# communication_module_20190819_to_aj-doy.net
KiCad netlist of a schematic drawn in EAGLE
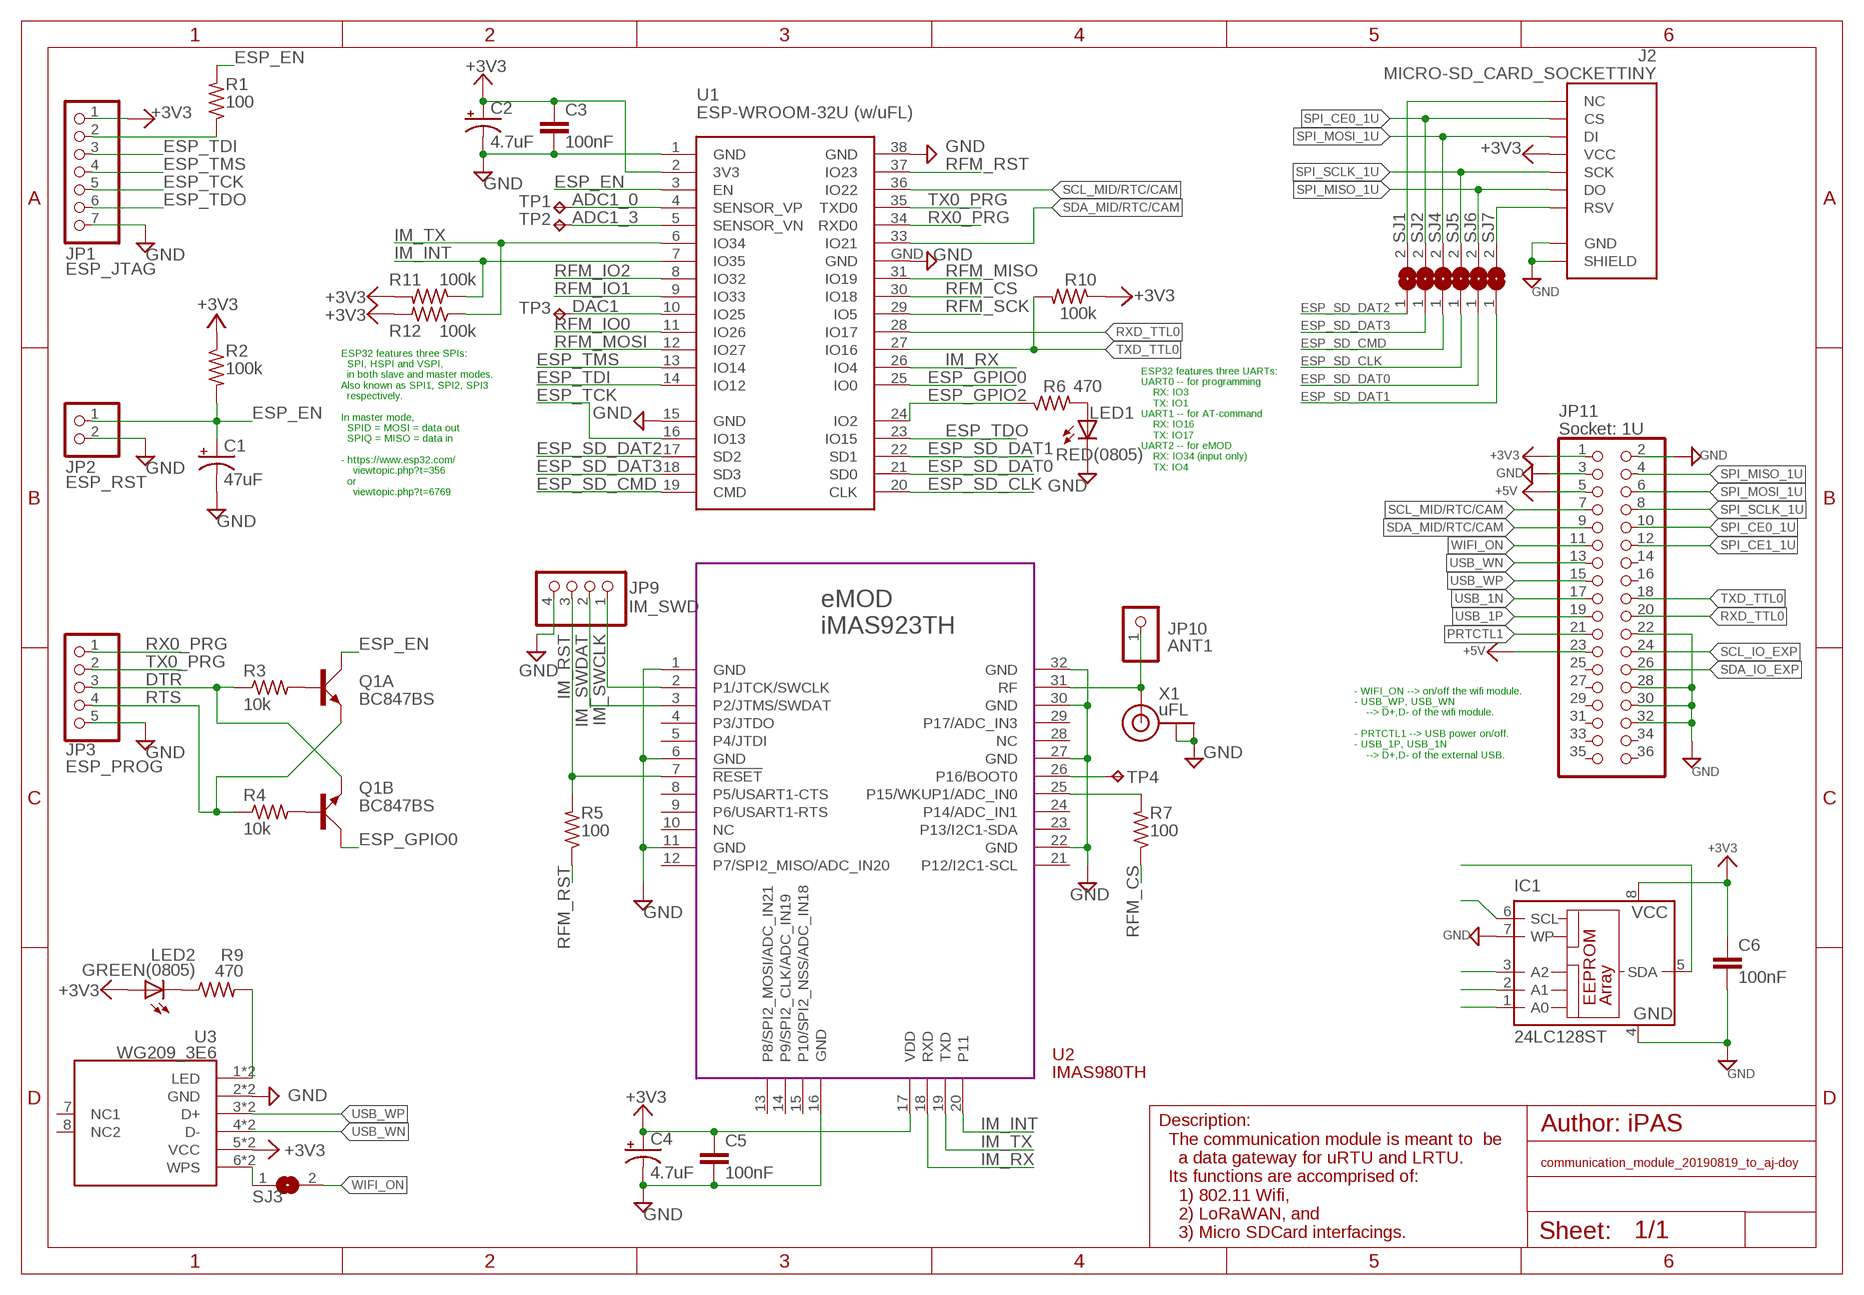
[diagram p0: schematic, sheet 1]

(export (version "E")
  (design (tool "Eeschema 10.0.6"))
  (components
    (comp (ref "C1")
      (value "47uF")
      (footprint "eagle-import:RCL_150CLZ-1014")
      (libsource (lib "eagle-import") (part "RCL_CPOL-US150CLZ-1014"))
    )
    (comp (ref "C2")
      (value "4.7uF")
      (footprint "eagle-import:RCL_150CLZ-1014")
      (libsource (lib "eagle-import") (part "RCL_CPOL-US150CLZ-1014"))
    )
    (comp (ref "C3")
      (value "100nF")
      (footprint "eagle-import:RCL_C1206")
      (libsource (lib "eagle-import") (part "RCL_C-EUC1206"))
    )
    (comp (ref "C4")
      (value "4.7uF")
      (footprint "eagle-import:RCL_150CLZ-1014")
      (libsource (lib "eagle-import") (part "RCL_CPOL-US150CLZ-1014"))
    )
    (comp (ref "C5")
      (value "100nF")
      (footprint "eagle-import:RCL_C1206")
      (libsource (lib "eagle-import") (part "RCL_C-EUC1206"))
    )
    (comp (ref "C6")
      (value "100nF")
      (footprint "eagle-import:RCL_C1206")
      (libsource (lib "eagle-import") (part "RCL_C-EUC1206"))
    )
    (comp (ref "IC1")
      (value "24LC128ST")
      (footprint "eagle-import:TSSOP8")
      (fields (field (name "MF") "MICROCHIP") (field (name "MPN") "24LC128-I/ST"))
      (libsource (lib "eagle-import") (part "24STLC128"))
    )
    (comp (ref "J2")
      (value "MICRO-SD_CARD_SOCKETTINY")
      (footprint "eagle-import:MICROSD_TINY")
      (libsource (lib "eagle-import") (part "MICRO-SD_CARD_SOCKETTINY"))
    )
    (comp (ref "JP1")
      (value "ESP_JTAG")
      (footprint "eagle-import:1X07")
      (libsource (lib "eagle-import") (part "PINHD-1X7"))
    )
    (comp (ref "JP2")
      (value "ESP_RST")
      (footprint "eagle-import:1X02")
      (libsource (lib "eagle-import") (part "PINHD-1X2"))
    )
    (comp (ref "JP3")
      (value "ESP_PROG")
      (footprint "eagle-import:1X05")
      (libsource (lib "eagle-import") (part "PINHD-1X5"))
    )
    (comp (ref "JP9")
      (value "IM_SWD")
      (footprint "eagle-import:1X04")
      (libsource (lib "eagle-import") (part "PINHD-1X4"))
    )
    (comp (ref "JP10")
      (value "ANT1")
      (footprint "eagle-import:1X01_ROUND")
      (libsource (lib "eagle-import") (part "HEADER-1X1ROUND"))
    )
    (comp (ref "JP11")
      (value "Socket: 1U")
      (footprint "eagle-import:2X18")
      (libsource (lib "eagle-import") (part "PINHD-2X18"))
    )
    (comp (ref "LED1")
      (value "RED(0805)")
      (footprint "eagle-import:CHIP-LED0805")
      (libsource (lib "eagle-import") (part "LEDCHIP-LED0805"))
    )
    (comp (ref "LED2")
      (value "GREEN(0805)")
      (footprint "eagle-import:CHIP-LED0805")
      (libsource (lib "eagle-import") (part "LEDCHIP-LED0805"))
    )
    (comp (ref "Q1")
      (value "BC847BS")
      (footprint "eagle-import:SOT363_PHILIPS")
      (libsource (lib "eagle-import") (part "BC847BS"))
    )
    (comp (ref "R1")
      (value "100")
      (footprint "eagle-import:RCL_M0805")
      (libsource (lib "eagle-import") (part "RCL_R-USM0805"))
    )
    (comp (ref "R2")
      (value "100k")
      (footprint "eagle-import:RCL_M0805")
      (libsource (lib "eagle-import") (part "RCL_R-USM0805"))
    )
    (comp (ref "R3")
      (value "10k")
      (footprint "eagle-import:RCL_M0805")
      (libsource (lib "eagle-import") (part "RCL_R-USM0805"))
    )
    (comp (ref "R4")
      (value "10k")
      (footprint "eagle-import:RCL_M0805")
      (libsource (lib "eagle-import") (part "RCL_R-USM0805"))
    )
    (comp (ref "R5")
      (value "100")
      (footprint "eagle-import:RCL_M0805")
      (libsource (lib "eagle-import") (part "RCL_R-USM0805"))
    )
    (comp (ref "R6")
      (value "470")
      (footprint "eagle-import:RCL_M0805")
      (libsource (lib "eagle-import") (part "RCL_R-USM0805"))
    )
    (comp (ref "R7")
      (value "100")
      (footprint "eagle-import:RCL_M0805")
      (libsource (lib "eagle-import") (part "RCL_R-USM0805"))
    )
    (comp (ref "R9")
      (value "470")
      (footprint "eagle-import:RCL_M0805")
      (libsource (lib "eagle-import") (part "RCL_R-USM0805"))
    )
    (comp (ref "R10")
      (value "100k")
      (footprint "eagle-import:RCL_M0805")
      (libsource (lib "eagle-import") (part "RCL_R-USM0805"))
    )
    (comp (ref "R11")
      (value "100k")
      (footprint "eagle-import:RCL_M0805")
      (libsource (lib "eagle-import") (part "RCL_R-USM0805"))
    )
    (comp (ref "R12")
      (value "100k")
      (footprint "eagle-import:RCL_M0805")
      (libsource (lib "eagle-import") (part "RCL_R-USM0805"))
    )
    (comp (ref "SJ1")
      (value "SOLDERJUMPERREFLOW")
      (footprint "eagle-import:SOLDERJUMPER_REFLOW")
      (libsource (lib "eagle-import") (part "SOLDERJUMPERREFLOW"))
    )
    (comp (ref "SJ2")
      (value "SOLDERJUMPERREFLOW")
      (footprint "eagle-import:SOLDERJUMPER_REFLOW")
      (libsource (lib "eagle-import") (part "SOLDERJUMPERREFLOW"))
    )
    (comp (ref "SJ3")
      (value "SOLDERJUMPERREFLOW")
      (footprint "eagle-import:SOLDERJUMPER_REFLOW")
      (libsource (lib "eagle-import") (part "SOLDERJUMPERREFLOW"))
    )
    (comp (ref "SJ4")
      (value "SOLDERJUMPERREFLOW")
      (footprint "eagle-import:SOLDERJUMPER_REFLOW")
      (libsource (lib "eagle-import") (part "SOLDERJUMPERREFLOW"))
    )
    (comp (ref "SJ5")
      (value "SOLDERJUMPERREFLOW")
      (footprint "eagle-import:SOLDERJUMPER_REFLOW")
      (libsource (lib "eagle-import") (part "SOLDERJUMPERREFLOW"))
    )
    (comp (ref "SJ6")
      (value "SOLDERJUMPERREFLOW")
      (footprint "eagle-import:SOLDERJUMPER_REFLOW")
      (libsource (lib "eagle-import") (part "SOLDERJUMPERREFLOW"))
    )
    (comp (ref "SJ7")
      (value "SOLDERJUMPERREFLOW")
      (footprint "eagle-import:SOLDERJUMPER_REFLOW")
      (libsource (lib "eagle-import") (part "SOLDERJUMPERREFLOW"))
    )
    (comp (ref "TP1")
      (value "TPB1,27")
      (footprint "eagle-import:B1,27")
      (libsource (lib "eagle-import") (part "TPB1,27"))
    )
    (comp (ref "TP2")
      (value "TPB1,27")
      (footprint "eagle-import:B1,27")
      (libsource (lib "eagle-import") (part "TPB1,27"))
    )
    (comp (ref "TP3")
      (value "TPB1,27")
      (footprint "eagle-import:B1,27")
      (libsource (lib "eagle-import") (part "TPB1,27"))
    )
    (comp (ref "TP4")
      (value "TPB1,27")
      (footprint "eagle-import:B1,27")
      (libsource (lib "eagle-import") (part "TPB1,27"))
    )
    (comp (ref "U1")
      (value "ESP-WROOM-32U (w/uFL)")
      (footprint "eagle-import:ESP-WROOM-32")
      (libsource (lib "eagle-import") (part "ESP-WROOM-32"))
    )
    (comp (ref "U2")
      (value "IMAS980TH")
      (footprint "eagle-import:IMAS923TH")
      (libsource (lib "eagle-import") (part "IMAS980TH"))
    )
    (comp (ref "U3")
      (value "WG209_3E6")
      (footprint "eagle-import:WG209")
      (libsource (lib "eagle-import") (part "WG209"))
    )
    (comp (ref "X1")
      (value "uFL")
      (footprint "eagle-import:U.FL")
      (libsource (lib "eagle-import") (part "ANTENNA_U.FL"))
    )
  )
  (nets
    (net (code "1") (name "+3V3") (class "Default")
      (node (ref "C2") (pin "+") (pinfunction "+_+") (pintype "passive"))
      (node (ref "C3") (pin "1") (pinfunction "1_1") (pintype "passive"))
      (node (ref "C4") (pin "+") (pinfunction "+_+") (pintype "passive"))
      (node (ref "C5") (pin "1") (pinfunction "1_1") (pintype "passive"))
      (node (ref "C6") (pin "1") (pinfunction "1_1") (pintype "passive"))
      (node (ref "IC1") (pin "8") (pinfunction "VCC_8") (pintype "power_in"))
      (node (ref "J2") (pin "4") (pinfunction "VCC_4") (pintype "bidirectional"))
      (node (ref "JP1") (pin "1") (pinfunction "1_1") (pintype "passive"))
      (node (ref "JP11") (pin "1") (pinfunction "1_1") (pintype "passive"))
      (node (ref "LED2") (pin "A") (pinfunction "A_A") (pintype "passive"))
      (node (ref "R10") (pin "1") (pinfunction "1_1") (pintype "passive"))
      (node (ref "R11") (pin "2") (pinfunction "2_2") (pintype "passive"))
      (node (ref "R12") (pin "2") (pinfunction "2_2") (pintype "passive"))
      (node (ref "R2") (pin "1") (pinfunction "1_1") (pintype "passive"))
      (node (ref "U1") (pin "2") (pinfunction "3V3_2") (pintype "power_in"))
      (node (ref "U2") (pin "17") (pinfunction "VDD_17") (pintype "power_in"))
      (node (ref "U3") (pin "5") (pinfunction "VCC_5") (pintype "power_in"))
      (node (ref "U3") (pin "5P") (pinfunction "VCC_5P") (pintype "power_in"))
    )
    (net (code "2") (name "+5V") (class "Default")
      (node (ref "JP11") (pin "23") (pinfunction "23_23") (pintype "passive"))
      (node (ref "JP11") (pin "5") (pinfunction "5_5") (pintype "passive"))
    )
    (net (code "3") (name "/ADC1_0") (class "Default")
      (node (ref "TP1") (pin "TP") (pinfunction "TP_TP") (pintype "input"))
      (node (ref "U1") (pin "4") (pinfunction "SENSOR_VP_4") (pintype "bidirectional"))
    )
    (net (code "4") (name "/ADC1_3") (class "Default")
      (node (ref "TP2") (pin "TP") (pinfunction "TP_TP") (pintype "input"))
      (node (ref "U1") (pin "5") (pinfunction "SENSOR_VN_5") (pintype "bidirectional"))
    )
    (net (code "5") (name "/DAC1") (class "Default")
      (node (ref "TP3") (pin "TP") (pinfunction "TP_TP") (pintype "input"))
      (node (ref "U1") (pin "10") (pinfunction "IO25_10") (pintype "bidirectional"))
    )
    (net (code "6") (name "/DTR") (class "Default")
      (node (ref "JP3") (pin "3") (pinfunction "3_3") (pintype "passive"))
      (node (ref "Q1") (pin "4") (pinfunction "E_4") (pintype "passive"))
      (node (ref "R3") (pin "1") (pinfunction "1_1") (pintype "passive"))
    )
    (net (code "7") (name "/ESP_EN") (class "Default")
      (node (ref "C1") (pin "+") (pinfunction "+_+") (pintype "passive"))
      (node (ref "JP2") (pin "1") (pinfunction "1_1") (pintype "passive"))
      (node (ref "Q1") (pin "6") (pinfunction "C_6") (pintype "passive"))
      (node (ref "R1") (pin "2") (pinfunction "2_2") (pintype "passive"))
      (node (ref "R2") (pin "2") (pinfunction "2_2") (pintype "passive"))
      (node (ref "U1") (pin "3") (pinfunction "EN_3") (pintype "input"))
    )
    (net (code "8") (name "/ESP_GPIO0") (class "Default")
      (node (ref "Q1") (pin "3") (pinfunction "C_3") (pintype "passive"))
      (node (ref "U1") (pin "25") (pinfunction "IO0_25") (pintype "bidirectional"))
    )
    (net (code "9") (name "/ESP_GPIO2") (class "Default")
      (node (ref "R6") (pin "1") (pinfunction "1_1") (pintype "passive"))
      (node (ref "U1") (pin "24") (pinfunction "IO2_24") (pintype "bidirectional"))
    )
    (net (code "10") (name "/ESP_SD_CLK") (class "Default")
      (node (ref "SJ5") (pin "1") (pinfunction "1_1") (pintype "passive"))
      (node (ref "U1") (pin "20") (pinfunction "CLK_20") (pintype "bidirectional"))
    )
    (net (code "11") (name "/ESP_SD_CMD") (class "Default")
      (node (ref "SJ4") (pin "1") (pinfunction "1_1") (pintype "passive"))
      (node (ref "U1") (pin "19") (pinfunction "CMD_19") (pintype "bidirectional"))
    )
    (net (code "12") (name "/ESP_SD_DAT0") (class "Default")
      (node (ref "SJ6") (pin "1") (pinfunction "1_1") (pintype "passive"))
      (node (ref "U1") (pin "21") (pinfunction "SD0_21") (pintype "bidirectional"))
    )
    (net (code "13") (name "/ESP_SD_DAT1") (class "Default")
      (node (ref "SJ7") (pin "1") (pinfunction "1_1") (pintype "passive"))
      (node (ref "U1") (pin "22") (pinfunction "SD1_22") (pintype "bidirectional"))
    )
    (net (code "14") (name "/ESP_SD_DAT2") (class "Default")
      (node (ref "SJ1") (pin "1") (pinfunction "1_1") (pintype "passive"))
      (node (ref "U1") (pin "17") (pinfunction "SD2_17") (pintype "bidirectional"))
    )
    (net (code "15") (name "/ESP_SD_DAT3") (class "Default")
      (node (ref "SJ2") (pin "1") (pinfunction "1_1") (pintype "passive"))
      (node (ref "U1") (pin "18") (pinfunction "SD3_18") (pintype "bidirectional"))
    )
    (net (code "16") (name "/ESP_TCK") (class "Default")
      (node (ref "JP1") (pin "5") (pinfunction "5_5") (pintype "passive"))
      (node (ref "U1") (pin "16") (pinfunction "IO13_16") (pintype "bidirectional"))
    )
    (net (code "17") (name "/ESP_TDI") (class "Default")
      (node (ref "JP1") (pin "3") (pinfunction "3_3") (pintype "passive"))
      (node (ref "U1") (pin "14") (pinfunction "IO12_14") (pintype "bidirectional"))
    )
    (net (code "18") (name "/ESP_TDO") (class "Default")
      (node (ref "JP1") (pin "6") (pinfunction "6_6") (pintype "passive"))
      (node (ref "U1") (pin "23") (pinfunction "IO15_23") (pintype "bidirectional"))
    )
    (net (code "19") (name "/ESP_TMS") (class "Default")
      (node (ref "JP1") (pin "4") (pinfunction "4_4") (pintype "passive"))
      (node (ref "U1") (pin "13") (pinfunction "IO14_13") (pintype "bidirectional"))
    )
    (net (code "20") (name "/IM_INT") (class "Default")
      (node (ref "R11") (pin "1") (pinfunction "1_1") (pintype "passive"))
      (node (ref "U1") (pin "7") (pinfunction "IO35_7") (pintype "bidirectional"))
      (node (ref "U2") (pin "20") (pinfunction "P11_20") (pintype "bidirectional"))
    )
    (net (code "21") (name "/IM_RST") (class "Default")
      (node (ref "JP9") (pin "3") (pinfunction "3_3") (pintype "passive"))
      (node (ref "R5") (pin "2") (pinfunction "2_2") (pintype "passive"))
      (node (ref "U2") (pin "7") (pinfunction "~{RESET}_7") (pintype "passive"))
    )
    (net (code "22") (name "/IM_RX") (class "Default")
      (node (ref "U1") (pin "26") (pinfunction "IO4_26") (pintype "bidirectional"))
      (node (ref "U2") (pin "18") (pinfunction "RXD_18") (pintype "bidirectional"))
    )
    (net (code "23") (name "/IM_SWCLK") (class "Default")
      (node (ref "JP9") (pin "1") (pinfunction "1_1") (pintype "passive"))
      (node (ref "U2") (pin "2") (pinfunction "P1/JTCK/SWCLK_2") (pintype "bidirectional"))
    )
    (net (code "24") (name "/IM_SWDAT") (class "Default")
      (node (ref "JP9") (pin "2") (pinfunction "2_2") (pintype "passive"))
      (node (ref "U2") (pin "3") (pinfunction "P2/JTMS/SWDAT_3") (pintype "bidirectional"))
    )
    (net (code "25") (name "/IM_TX") (class "Default")
      (node (ref "R12") (pin "1") (pinfunction "1_1") (pintype "passive"))
      (node (ref "U1") (pin "6") (pinfunction "IO34_6") (pintype "bidirectional"))
      (node (ref "U2") (pin "19") (pinfunction "TXD_19") (pintype "bidirectional"))
    )
    (net (code "26") (name "/RFM_CS") (class "Default")
      (node (ref "R7") (pin "1") (pinfunction "1_1") (pintype "passive"))
      (node (ref "U1") (pin "30") (pinfunction "IO18_30") (pintype "bidirectional"))
    )
    (net (code "27") (name "/RFM_IO0") (class "Default")
      (node (ref "U1") (pin "11") (pinfunction "IO26_11") (pintype "bidirectional"))
    )
    (net (code "28") (name "/RFM_IO1") (class "Default")
      (node (ref "U1") (pin "9") (pinfunction "IO33_9") (pintype "bidirectional"))
    )
    (net (code "29") (name "/RFM_IO2") (class "Default")
      (node (ref "U1") (pin "8") (pinfunction "IO32_8") (pintype "bidirectional"))
    )
    (net (code "30") (name "/RFM_MISO") (class "Default")
      (node (ref "U1") (pin "31") (pinfunction "IO19_31") (pintype "bidirectional"))
    )
    (net (code "31") (name "/RFM_MOSI") (class "Default")
      (node (ref "U1") (pin "12") (pinfunction "IO27_12") (pintype "bidirectional"))
    )
    (net (code "32") (name "/RFM_RST") (class "Default")
      (node (ref "R5") (pin "1") (pinfunction "1_1") (pintype "passive"))
      (node (ref "U1") (pin "37") (pinfunction "IO23_37") (pintype "bidirectional"))
    )
    (net (code "33") (name "/RFM_SCK") (class "Default")
      (node (ref "U1") (pin "29") (pinfunction "IO5_29") (pintype "bidirectional"))
    )
    (net (code "34") (name "/RTS") (class "Default")
      (node (ref "JP3") (pin "4") (pinfunction "4_4") (pintype "passive"))
      (node (ref "Q1") (pin "1") (pinfunction "E_1") (pintype "passive"))
      (node (ref "R4") (pin "1") (pinfunction "1_1") (pintype "passive"))
    )
    (net (code "35") (name "/RX0_PRG") (class "Default")
      (node (ref "JP3") (pin "1") (pinfunction "1_1") (pintype "passive"))
      (node (ref "U1") (pin "34") (pinfunction "RXD0_34") (pintype "bidirectional"))
    )
    (net (code "36") (name "/TX0_PRG") (class "Default")
      (node (ref "JP3") (pin "2") (pinfunction "2_2") (pintype "passive"))
      (node (ref "U1") (pin "35") (pinfunction "TXD0_35") (pintype "bidirectional"))
    )
    (net (code "37") (name "GND") (class "Default")
      (node (ref "C1") (pin "-") (pinfunction "-_-") (pintype "passive"))
      (node (ref "C2") (pin "-") (pinfunction "-_-") (pintype "passive"))
      (node (ref "C3") (pin "2") (pinfunction "2_2") (pintype "passive"))
      (node (ref "C4") (pin "-") (pinfunction "-_-") (pintype "passive"))
      (node (ref "C5") (pin "2") (pinfunction "2_2") (pintype "passive"))
      (node (ref "C6") (pin "2") (pinfunction "2_2") (pintype "passive"))
      (node (ref "IC1") (pin "4") (pinfunction "GND_4") (pintype "power_in"))
      (node (ref "IC1") (pin "7") (pinfunction "WP_7") (pintype "input"))
      (node (ref "J2") (pin "6") (pinfunction "GND_6") (pintype "bidirectional"))
      (node (ref "J2") (pin "GND1") (pinfunction "SHIELD_GND1") (pintype "bidirectional"))
      (node (ref "J2") (pin "GND2") (pinfunction "SHIELD_GND2") (pintype "bidirectional"))
      (node (ref "J2") (pin "GND3") (pinfunction "SHIELD_GND3") (pintype "bidirectional"))
      (node (ref "J2") (pin "GND4") (pinfunction "SHIELD_GND4") (pintype "bidirectional"))
      (node (ref "J2") (pin "GND5") (pinfunction "SHIELD_GND5") (pintype "bidirectional"))
      (node (ref "J2") (pin "GND6") (pinfunction "SHIELD_GND6") (pintype "bidirectional"))
      (node (ref "JP1") (pin "7") (pinfunction "7_7") (pintype "passive"))
      (node (ref "JP11") (pin "2") (pinfunction "2_2") (pintype "passive"))
      (node (ref "JP11") (pin "22") (pinfunction "22_22") (pintype "passive"))
      (node (ref "JP11") (pin "28") (pinfunction "28_28") (pintype "passive"))
      (node (ref "JP11") (pin "3") (pinfunction "3_3") (pintype "passive"))
      (node (ref "JP11") (pin "30") (pinfunction "30_30") (pintype "passive"))
      (node (ref "JP11") (pin "32") (pinfunction "32_32") (pintype "passive"))
      (node (ref "JP2") (pin "2") (pinfunction "2_2") (pintype "passive"))
      (node (ref "JP3") (pin "5") (pinfunction "5_5") (pintype "passive"))
      (node (ref "JP9") (pin "4") (pinfunction "4_4") (pintype "passive"))
      (node (ref "LED1") (pin "C") (pinfunction "C_C") (pintype "passive"))
      (node (ref "U1") (pin "1") (pinfunction "GND_1") (pintype "power_in"))
      (node (ref "U1") (pin "15") (pinfunction "GND_15") (pintype "power_in"))
      (node (ref "U1") (pin "38") (pinfunction "GND_38") (pintype "power_in"))
      (node (ref "U1") (pin "GND") (pinfunction "GND_GND") (pintype "power_in"))
      (node (ref "U2") (pin "1") (pinfunction "GND_1") (pintype "power_in"))
      (node (ref "U2") (pin "11") (pinfunction "GND_11") (pintype "power_in"))
      (node (ref "U2") (pin "16") (pinfunction "GND_16") (pintype "power_in"))
      (node (ref "U2") (pin "22") (pinfunction "GND_22") (pintype "power_in"))
      (node (ref "U2") (pin "27") (pinfunction "GND_27") (pintype "power_in"))
      (node (ref "U2") (pin "30") (pinfunction "GND_30") (pintype "power_in"))
      (node (ref "U2") (pin "32") (pinfunction "GND_32") (pintype "power_in"))
      (node (ref "U2") (pin "6") (pinfunction "GND_6") (pintype "power_in"))
      (node (ref "U3") (pin "2") (pinfunction "GND_2") (pintype "power_in"))
      (node (ref "U3") (pin "2P") (pinfunction "GND_2P") (pintype "power_in"))
      (node (ref "X1") (pin "1") (pinfunction "GND_1") (pintype "passive"))
      (node (ref "X1") (pin "2") (pinfunction "GND_2") (pintype "passive"))
    )
    (net (code "38") (name "Net-(J2-NC)") (class "Default")
      (node (ref "J2") (pin "9") (pinfunction "NC_9") (pintype "bidirectional"))
      (node (ref "SJ1") (pin "2") (pinfunction "2_2") (pintype "passive"))
    )
    (net (code "39") (name "Net-(J2-RSV-Pad1)") (class "Default")
      (node (ref "J2") (pin "1") (pinfunction "RSV_1") (pintype "bidirectional"))
      (node (ref "J2") (pin "8") (pinfunction "RSV_8") (pintype "bidirectional"))
      (node (ref "SJ7") (pin "2") (pinfunction "2_2") (pintype "passive"))
    )
    (net (code "40") (name "Net-(JP1-Pad2)") (class "Default")
      (node (ref "JP1") (pin "2") (pinfunction "2_2") (pintype "passive"))
      (node (ref "R1") (pin "1") (pinfunction "1_1") (pintype "passive"))
    )
    (net (code "41") (name "Net-(LED1-PadA)") (class "Default")
      (node (ref "LED1") (pin "A") (pinfunction "A_A") (pintype "passive"))
      (node (ref "R6") (pin "2") (pinfunction "2_2") (pintype "passive"))
    )
    (net (code "42") (name "Net-(LED2-PadC)") (class "Default")
      (node (ref "LED2") (pin "C") (pinfunction "C_C") (pintype "passive"))
      (node (ref "R9") (pin "1") (pinfunction "1_1") (pintype "passive"))
    )
    (net (code "43") (name "Net-(Q1A-B)") (class "Default")
      (node (ref "Q1") (pin "2") (pinfunction "B_2") (pintype "passive"))
      (node (ref "R3") (pin "2") (pinfunction "2_2") (pintype "passive"))
    )
    (net (code "44") (name "Net-(Q1B-B)") (class "Default")
      (node (ref "Q1") (pin "5") (pinfunction "B_5") (pintype "passive"))
      (node (ref "R4") (pin "2") (pinfunction "2_2") (pintype "passive"))
    )
    (net (code "45") (name "Net-(R9-Pad2)") (class "Default")
      (node (ref "R9") (pin "2") (pinfunction "2_2") (pintype "passive"))
      (node (ref "U3") (pin "1") (pinfunction "LED_1") (pintype "bidirectional"))
      (node (ref "U3") (pin "1P") (pinfunction "LED_1P") (pintype "bidirectional"))
    )
    (net (code "46") (name "Net-(SJ3-Pad1)") (class "Default")
      (node (ref "SJ3") (pin "1") (pinfunction "1_1") (pintype "passive"))
      (node (ref "U3") (pin "6") (pinfunction "WPS_6") (pintype "bidirectional"))
      (node (ref "U3") (pin "6P") (pinfunction "WPS_6P") (pintype "bidirectional"))
    )
    (net (code "47") (name "Net-(U2-P15{slash}WKUP1{slash}ADC_IN0)") (class "Default")
      (node (ref "R7") (pin "2") (pinfunction "2_2") (pintype "passive"))
      (node (ref "U2") (pin "25") (pinfunction "P15/WKUP1/ADC_IN0_25") (pintype "bidirectional"))
    )
    (net (code "48") (name "Net-(U2-P16{slash}BOOT0)") (class "Default")
      (node (ref "TP4") (pin "TP") (pinfunction "TP_TP") (pintype "input"))
      (node (ref "U2") (pin "26") (pinfunction "P16/BOOT0_26") (pintype "passive"))
    )
    (net (code "49") (name "Net-(U2-RF)") (class "Default")
      (node (ref "JP10") (pin "1") (pinfunction "1_1") (pintype "passive"))
      (node (ref "U2") (pin "31") (pinfunction "RF_31") (pintype "bidirectional"))
      (node (ref "X1") (pin "3") (pinfunction "SIGNAL_3") (pintype "passive"))
    )
    (net (code "50") (name "PRTCTL1") (class "Default")
      (node (ref "JP11") (pin "21") (pinfunction "21_21") (pintype "passive"))
    )
    (net (code "51") (name "RXD_TTL0") (class "Default")
      (node (ref "JP11") (pin "20") (pinfunction "20_20") (pintype "passive"))
      (node (ref "U1") (pin "28") (pinfunction "IO17_28") (pintype "bidirectional"))
    )
    (net (code "52") (name "SCL_IO_EXP") (class "Default")
      (node (ref "JP11") (pin "24") (pinfunction "24_24") (pintype "passive"))
    )
    (net (code "53") (name "SCL_MID{slash}RTC{slash}CAM") (class "Default")
      (node (ref "JP11") (pin "7") (pinfunction "7_7") (pintype "passive"))
      (node (ref "U1") (pin "36") (pinfunction "IO22_36") (pintype "bidirectional"))
    )
    (net (code "54") (name "SDA_IO_EXP") (class "Default")
      (node (ref "JP11") (pin "26") (pinfunction "26_26") (pintype "passive"))
    )
    (net (code "55") (name "SDA_MID{slash}RTC{slash}CAM") (class "Default")
      (node (ref "JP11") (pin "9") (pinfunction "9_9") (pintype "passive"))
      (node (ref "U1") (pin "33") (pinfunction "IO21_33") (pintype "bidirectional"))
    )
    (net (code "56") (name "SPI_CE0_1U") (class "Default")
      (node (ref "J2") (pin "2") (pinfunction "CS_2") (pintype "bidirectional"))
      (node (ref "JP11") (pin "10") (pinfunction "10_10") (pintype "passive"))
      (node (ref "SJ2") (pin "2") (pinfunction "2_2") (pintype "passive"))
    )
    (net (code "57") (name "SPI_CE1_1U") (class "Default")
      (node (ref "JP11") (pin "12") (pinfunction "12_12") (pintype "passive"))
    )
    (net (code "58") (name "SPI_MISO_1U") (class "Default")
      (node (ref "J2") (pin "7") (pinfunction "DO_7") (pintype "bidirectional"))
      (node (ref "JP11") (pin "4") (pinfunction "4_4") (pintype "passive"))
      (node (ref "SJ6") (pin "2") (pinfunction "2_2") (pintype "passive"))
    )
    (net (code "59") (name "SPI_MOSI_1U") (class "Default")
      (node (ref "J2") (pin "3") (pinfunction "DI_3") (pintype "bidirectional"))
      (node (ref "JP11") (pin "6") (pinfunction "6_6") (pintype "passive"))
      (node (ref "SJ4") (pin "2") (pinfunction "2_2") (pintype "passive"))
    )
    (net (code "60") (name "SPI_SCLK_1U") (class "Default")
      (node (ref "J2") (pin "5") (pinfunction "SCK_5") (pintype "bidirectional"))
      (node (ref "JP11") (pin "8") (pinfunction "8_8") (pintype "passive"))
      (node (ref "SJ5") (pin "2") (pinfunction "2_2") (pintype "passive"))
    )
    (net (code "61") (name "TXD_TTL0") (class "Default")
      (node (ref "JP11") (pin "18") (pinfunction "18_18") (pintype "passive"))
      (node (ref "R10") (pin "2") (pinfunction "2_2") (pintype "passive"))
      (node (ref "U1") (pin "27") (pinfunction "IO16_27") (pintype "bidirectional"))
    )
    (net (code "62") (name "USB_1N") (class "Default")
      (node (ref "JP11") (pin "17") (pinfunction "17_17") (pintype "passive"))
    )
    (net (code "63") (name "USB_1P") (class "Default")
      (node (ref "JP11") (pin "19") (pinfunction "19_19") (pintype "passive"))
    )
    (net (code "64") (name "USB_WN") (class "Default")
      (node (ref "JP11") (pin "13") (pinfunction "13_13") (pintype "passive"))
      (node (ref "U3") (pin "4") (pinfunction "D-_4") (pintype "bidirectional"))
      (node (ref "U3") (pin "4P") (pinfunction "D-_4P") (pintype "bidirectional"))
    )
    (net (code "65") (name "USB_WP") (class "Default")
      (node (ref "JP11") (pin "15") (pinfunction "15_15") (pintype "passive"))
      (node (ref "U3") (pin "3") (pinfunction "D+_3") (pintype "bidirectional"))
      (node (ref "U3") (pin "3P") (pinfunction "D+_3P") (pintype "bidirectional"))
    )
    (net (code "66") (name "WIFI_ON") (class "Default")
      (node (ref "JP11") (pin "11") (pinfunction "11_11") (pintype "passive"))
      (node (ref "SJ3") (pin "2") (pinfunction "2_2") (pintype "passive"))
    )
    (net (code "67") (name "unconnected-(IC1-A0-Pad1)") (class "Default")
      (node (ref "IC1") (pin "1") (pinfunction "A0_1") (pintype "input"))
    )
    (net (code "68") (name "unconnected-(IC1-A1-Pad2)") (class "Default")
      (node (ref "IC1") (pin "2") (pinfunction "A1_2") (pintype "input"))
    )
    (net (code "69") (name "unconnected-(IC1-A2-Pad3)") (class "Default")
      (node (ref "IC1") (pin "3") (pinfunction "A2_3") (pintype "input"))
    )
    (net (code "70") (name "unconnected-(IC1-SCL-Pad6)") (class "Default")
      (node (ref "IC1") (pin "6") (pinfunction "SCL_6") (pintype "input"))
    )
    (net (code "71") (name "unconnected-(IC1-SDA-Pad5)") (class "Default")
      (node (ref "IC1") (pin "5") (pinfunction "SDA_5") (pintype "bidirectional"))
    )
    (net (code "72") (name "unconnected-(JP11-Pad14)") (class "Default")
      (node (ref "JP11") (pin "14") (pinfunction "14_14") (pintype "passive"))
    )
    (net (code "73") (name "unconnected-(JP11-Pad16)") (class "Default")
      (node (ref "JP11") (pin "16") (pinfunction "16_16") (pintype "passive"))
    )
    (net (code "74") (name "unconnected-(JP11-Pad25)") (class "Default")
      (node (ref "JP11") (pin "25") (pinfunction "25_25") (pintype "passive"))
    )
    (net (code "75") (name "unconnected-(JP11-Pad27)") (class "Default")
      (node (ref "JP11") (pin "27") (pinfunction "27_27") (pintype "passive"))
    )
    (net (code "76") (name "unconnected-(JP11-Pad29)") (class "Default")
      (node (ref "JP11") (pin "29") (pinfunction "29_29") (pintype "passive"))
    )
    (net (code "77") (name "unconnected-(JP11-Pad31)") (class "Default")
      (node (ref "JP11") (pin "31") (pinfunction "31_31") (pintype "passive"))
    )
    (net (code "78") (name "unconnected-(JP11-Pad33)") (class "Default")
      (node (ref "JP11") (pin "33") (pinfunction "33_33") (pintype "passive"))
    )
    (net (code "79") (name "unconnected-(JP11-Pad34)") (class "Default")
      (node (ref "JP11") (pin "34") (pinfunction "34_34") (pintype "passive"))
    )
    (net (code "80") (name "unconnected-(JP11-Pad35)") (class "Default")
      (node (ref "JP11") (pin "35") (pinfunction "35_35") (pintype "passive"))
    )
    (net (code "81") (name "unconnected-(JP11-Pad36)") (class "Default")
      (node (ref "JP11") (pin "36") (pinfunction "36_36") (pintype "passive"))
    )
    (net (code "82") (name "unconnected-(U2-NC-Pad10)") (class "Default")
      (node (ref "U2") (pin "10") (pinfunction "NC_10") (pintype "no_connect"))
    )
    (net (code "83") (name "unconnected-(U2-NC-Pad28)") (class "Default")
      (node (ref "U2") (pin "28") (pinfunction "NC_28") (pintype "no_connect"))
    )
    (net (code "84") (name "unconnected-(U2-P3{slash}JTDO-Pad4)") (class "Default")
      (node (ref "U2") (pin "4") (pinfunction "P3/JTDO_4") (pintype "bidirectional"))
    )
    (net (code "85") (name "unconnected-(U2-P4{slash}JTDI-Pad5)") (class "Default")
      (node (ref "U2") (pin "5") (pinfunction "P4/JTDI_5") (pintype "bidirectional"))
    )
    (net (code "86") (name "unconnected-(U2-P5{slash}USART1-CTS-Pad8)") (class "Default")
      (node (ref "U2") (pin "8") (pinfunction "P5/USART1-CTS_8") (pintype "bidirectional"))
    )
    (net (code "87") (name "unconnected-(U2-P6{slash}USART1-RTS-Pad9)") (class "Default")
      (node (ref "U2") (pin "9") (pinfunction "P6/USART1-RTS_9") (pintype "bidirectional"))
    )
    (net (code "88") (name "unconnected-(U2-P7{slash}SPI2_MISO{slash}ADC_IN20-Pad12)") (class "Default")
      (node (ref "U2") (pin "12") (pinfunction "P7/SPI2_MISO/ADC_IN20_12") (pintype "bidirectional"))
    )
    (net (code "89") (name "unconnected-(U2-P8{slash}SPI2_MOSI{slash}ADC_IN21-Pad13)") (class "Default")
      (node (ref "U2") (pin "13") (pinfunction "P8/SPI2_MOSI/ADC_IN21_13") (pintype "bidirectional"))
    )
    (net (code "90") (name "unconnected-(U2-P9{slash}SPI2_CLK{slash}ADC_IN19-Pad14)") (class "Default")
      (node (ref "U2") (pin "14") (pinfunction "P9/SPI2_CLK/ADC_IN19_14") (pintype "bidirectional"))
    )
    (net (code "91") (name "unconnected-(U2-P10{slash}SPI2_NSS{slash}ADC_IN18-Pad15)") (class "Default")
      (node (ref "U2") (pin "15") (pinfunction "P10/SPI2_NSS/ADC_IN18_15") (pintype "bidirectional"))
    )
    (net (code "92") (name "unconnected-(U2-P12{slash}I2C1-SCL-Pad21)") (class "Default")
      (node (ref "U2") (pin "21") (pinfunction "P12/I2C1-SCL_21") (pintype "bidirectional"))
    )
    (net (code "93") (name "unconnected-(U2-P13{slash}I2C1-SDA-Pad23)") (class "Default")
      (node (ref "U2") (pin "23") (pinfunction "P13/I2C1-SDA_23") (pintype "bidirectional"))
    )
    (net (code "94") (name "unconnected-(U2-P14{slash}ADC_IN1-Pad24)") (class "Default")
      (node (ref "U2") (pin "24") (pinfunction "P14/ADC_IN1_24") (pintype "bidirectional"))
    )
    (net (code "95") (name "unconnected-(U2-P17{slash}ADC_IN3-Pad29)") (class "Default")
      (node (ref "U2") (pin "29") (pinfunction "P17/ADC_IN3_29") (pintype "bidirectional"))
    )
    (net (code "96") (name "unconnected-(U3-NC1-Pad7)") (class "Default")
      (node (ref "U3") (pin "7") (pinfunction "NC1_7") (pintype "no_connect"))
    )
    (net (code "97") (name "unconnected-(U3-NC2-Pad8)") (class "Default")
      (node (ref "U3") (pin "8") (pinfunction "NC2_8") (pintype "no_connect"))
    )
  )
)
